# SRH_V2_0.net
KiCad netlist of a schematic drawn in EasyEDA Pro
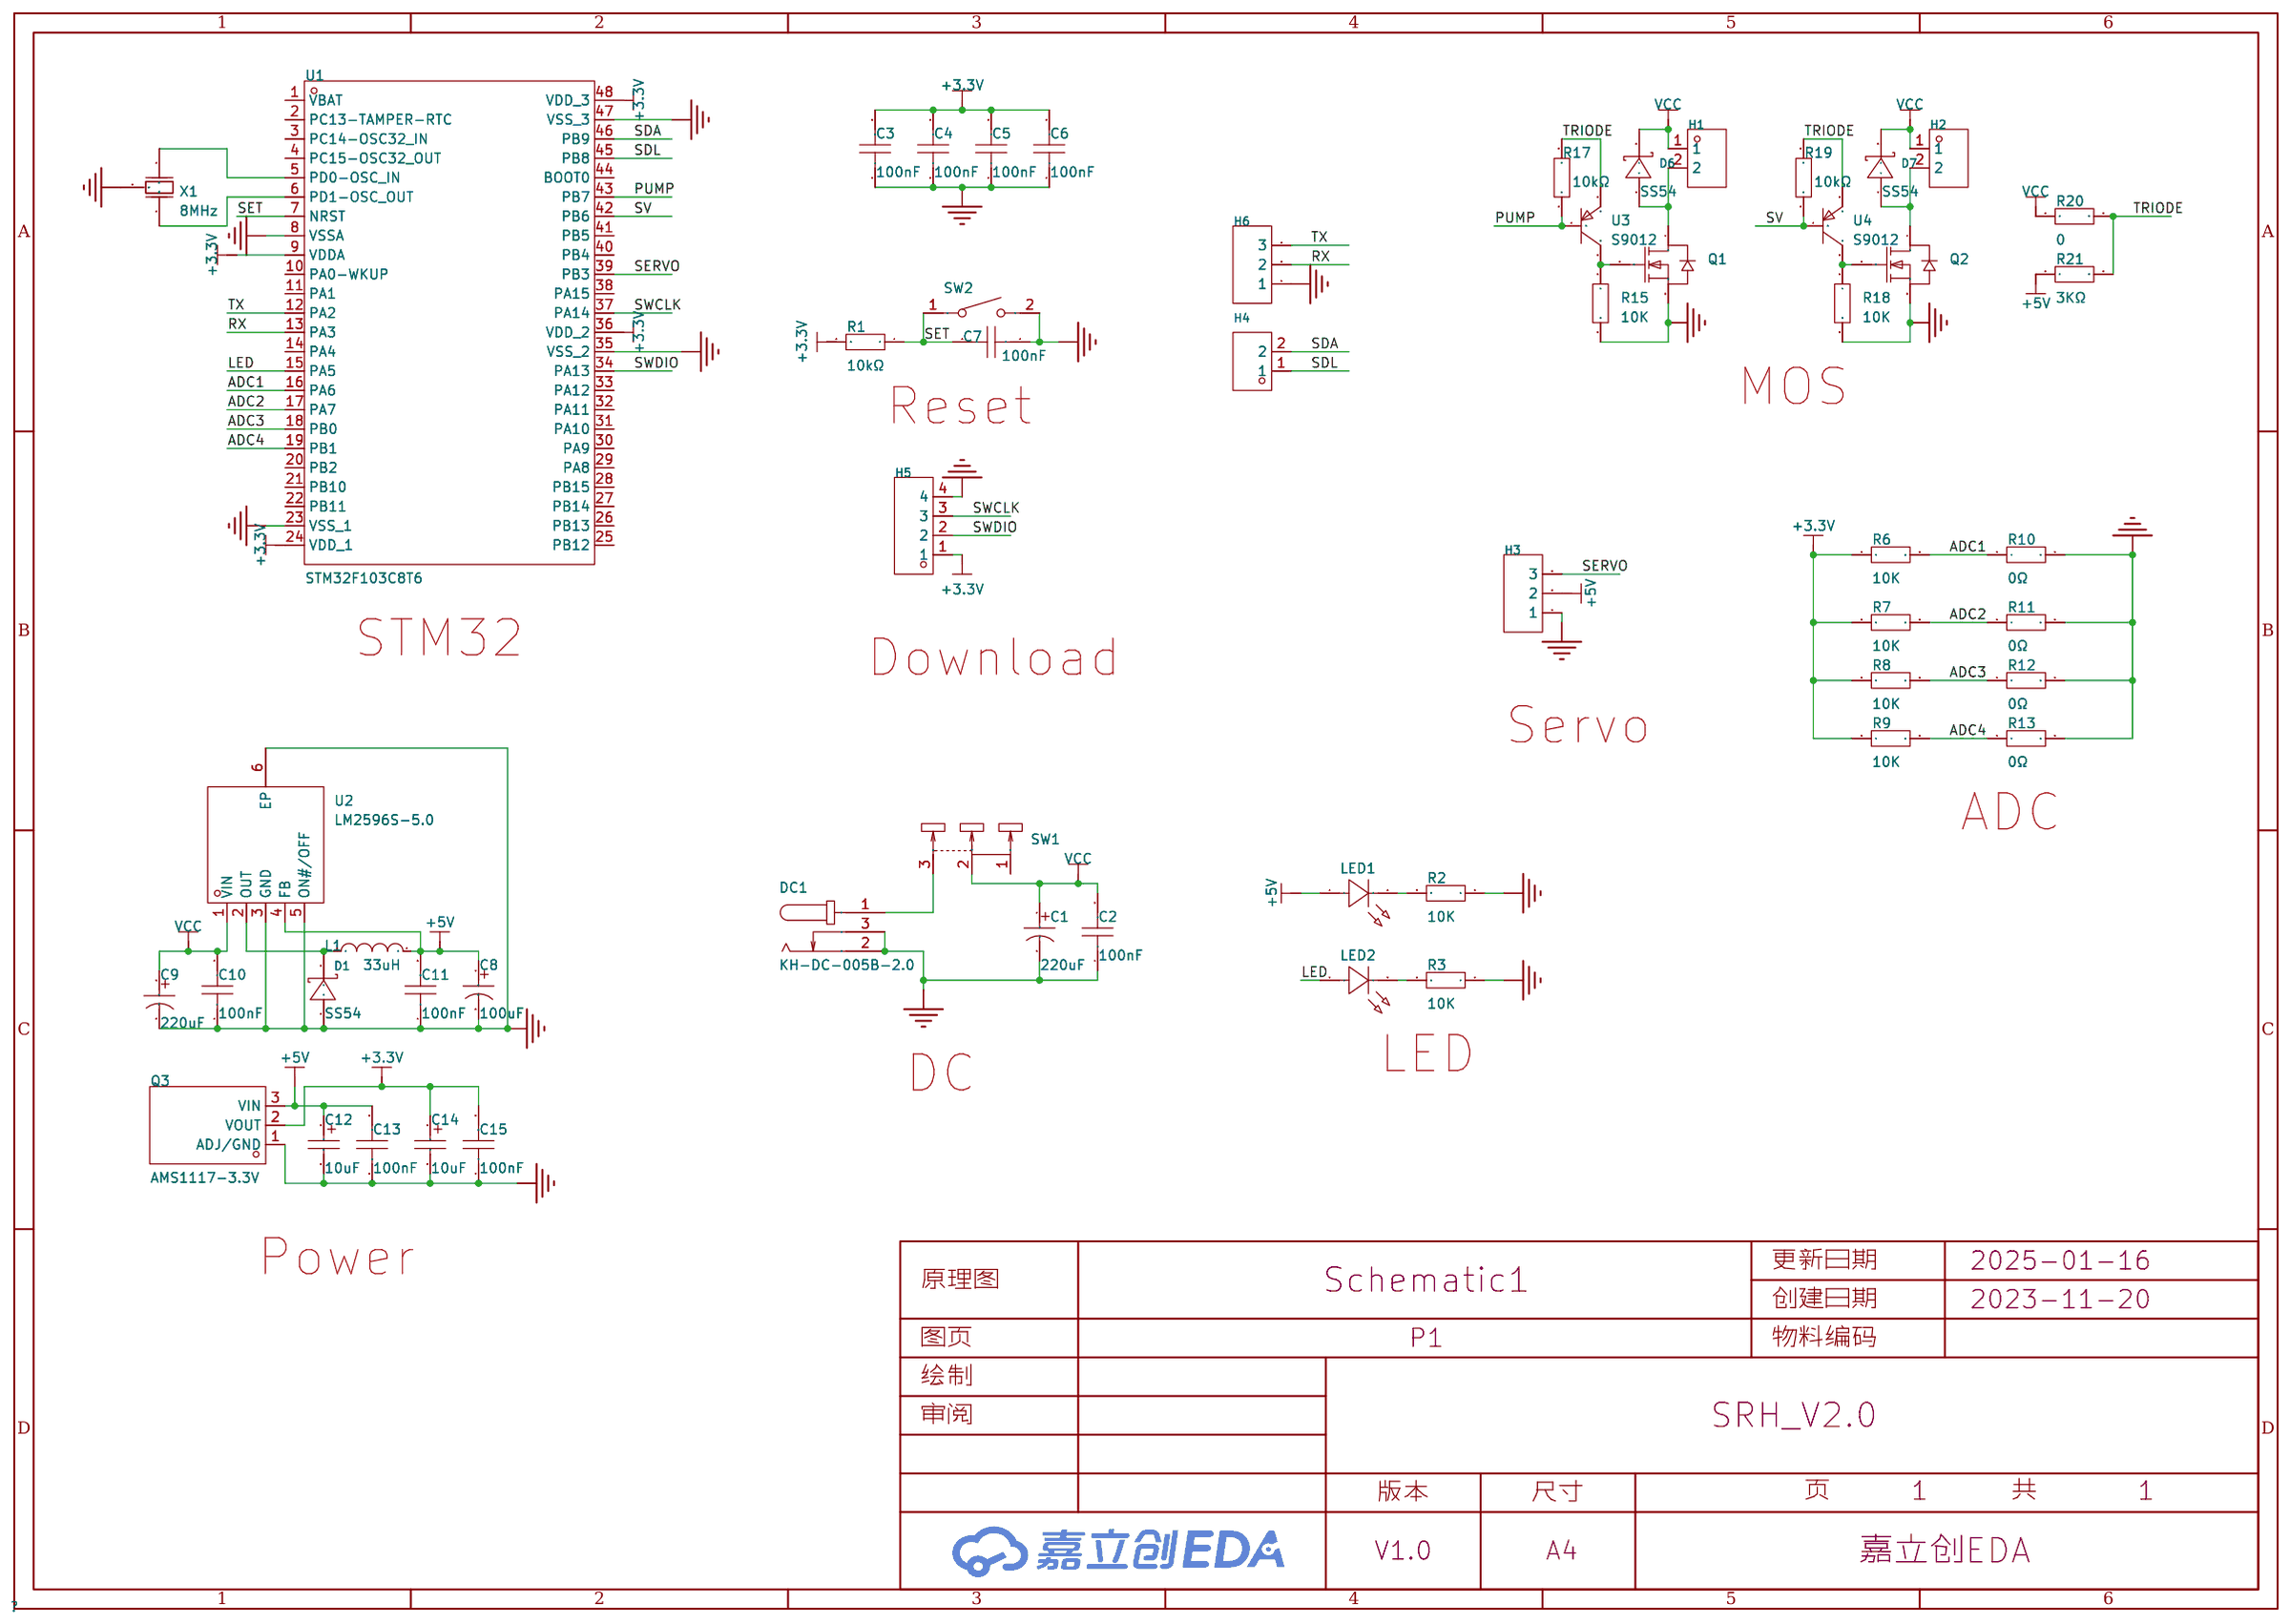
[diagram p0: schematic sheet]

(export (version "E")
  (design (tool "Eeschema 10.0.6"))
  (components
    (comp (ref "C1")
      (value "220uF")
      (footprint "easyedapro:CAP-TH_BD6.3-P2.50-D1.0-FD")
      (description "容值:220uF;精度:±20%;额定电压:16V;纹波电流:-;等效串联电阻:-;")
      (fields
        (field (name "Manufacturer Part") "KS227M016E07RR0VH2FP0")
        (field (name "Manufacturer") "CX(承兴)")
      )
      (libsource (lib "easyedapro") (part "220uF 16V 6.3*7"))
    )
    (comp (ref "C2")
      (value "100nF")
      (footprint "easyedapro:C0603")
      (libsource (lib "easyedapro") (part "CapAcitance"))
    )
    (comp (ref "C3")
      (value "100nF")
      (footprint "easyedapro:C0603")
      (description "容值:100nF;精度:±10%;额定电压:50V;材质(温度系数):X7R;")
      (fields
        (field (name "Manufacturer Part") "CC0603KRX7R9BB104")
        (field (name "Manufacturer") "YAGEO(国巨)")
      )
      (libsource (lib "easyedapro") (part "CC0603KRX7R9BB104"))
    )
    (comp (ref "C4")
      (value "100nF")
      (footprint "easyedapro:C0603")
      (description "容值:100nF;精度:±10%;额定电压:50V;材质(温度系数):X7R;")
      (fields
        (field (name "Manufacturer Part") "CC0603KRX7R9BB104")
        (field (name "Manufacturer") "YAGEO(国巨)")
      )
      (libsource (lib "easyedapro") (part "CC0603KRX7R9BB104"))
    )
    (comp (ref "C5")
      (value "100nF")
      (footprint "easyedapro:C0603")
      (description "容值:100nF;精度:±10%;额定电压:50V;材质(温度系数):X7R;")
      (fields
        (field (name "Manufacturer Part") "CC0603KRX7R9BB104")
        (field (name "Manufacturer") "YAGEO(国巨)")
      )
      (libsource (lib "easyedapro") (part "CC0603KRX7R9BB104"))
    )
    (comp (ref "C6")
      (value "100nF")
      (footprint "easyedapro:C0603")
      (description "容值:100nF;精度:±10%;额定电压:50V;材质(温度系数):X7R;")
      (fields
        (field (name "Manufacturer Part") "CC0603KRX7R9BB104")
        (field (name "Manufacturer") "YAGEO(国巨)")
      )
      (libsource (lib "easyedapro") (part "CC0603KRX7R9BB104"))
    )
    (comp (ref "C7")
      (value "100nF")
      (footprint "easyedapro:C0603")
      (description "容值:100nF;精度:±10%;额定电压:50V;材质(温度系数):X7R;")
      (fields
        (field (name "Manufacturer Part") "CC0603KRX7R9BB104")
        (field (name "Manufacturer") "YAGEO(国巨)")
      )
      (libsource (lib "easyedapro") (part "CC0603KRX7R9BB104"))
    )
    (comp (ref "C8")
      (value "100uF")
      (footprint "easyedapro:CAP-TH_BD5.0-P2.00-D0.8-FD")
      (description "容值:100uF;精度:±20%;额定电压:10V;纹波电流:50mA@120Hz;等效串联电阻:-;")
      (fields
        (field (name "Manufacturer Part") "KS107M010D07RR0VH2FP0")
        (field (name "Manufacturer") "CX(承兴)")
      )
      (libsource (lib "easyedapro") (part "100uF 10V 5*7"))
    )
    (comp (ref "C9")
      (value "220uF")
      (footprint "easyedapro:CAP-TH_BD6.3-P2.50-D1.0-FD")
      (description "容值:220uF;精度:±20%;额定电压:16V;纹波电流:-;等效串联电阻:-;")
      (fields
        (field (name "Manufacturer Part") "KS227M016E07RR0VH2FP0")
        (field (name "Manufacturer") "CX(承兴)")
      )
      (libsource (lib "easyedapro") (part "220uF 16V 6.3*7"))
    )
    (comp (ref "C10")
      (value "100nF")
      (footprint "easyedapro:C0603")
      (description "容值:100nF;精度:±10%;额定电压:50V;材质(温度系数):X7R;")
      (fields
        (field (name "Manufacturer Part") "CC0603KRX7R9BB104")
        (field (name "Manufacturer") "YAGEO(国巨)")
      )
      (libsource (lib "easyedapro") (part "CC0603KRX7R9BB104"))
    )
    (comp (ref "C11")
      (value "100nF")
      (footprint "easyedapro:C0603")
      (description "容值:100nF;精度:±10%;额定电压:50V;材质(温度系数):X7R;")
      (fields
        (field (name "Manufacturer Part") "CC0603KRX7R9BB104")
        (field (name "Manufacturer") "YAGEO(国巨)")
      )
      (libsource (lib "easyedapro") (part "CC0603KRX7R9BB104"))
    )
    (comp (ref "C12")
      (value "10uF")
      (footprint "easyedapro:CASE-A_3216")
      (description "容值:10uF;精度:±10%;额定电压:16V;等效串联电阻:7Ω@100kHz;")
      (fields
        (field (name "Manufacturer Part") "CA45A-A-16V-10uF-K")
        (field (name "Manufacturer") "CEC(振华新云)")
      )
      (libsource (lib "easyedapro") (part "CA45A-A-16V-10UF-K"))
    )
    (comp (ref "C13")
      (value "100nF")
      (footprint "easyedapro:C0603")
      (libsource (lib "easyedapro") (part "CapAcitance"))
    )
    (comp (ref "C14")
      (value "10uF")
      (footprint "easyedapro:CASE-A_3216")
      (description "容值:10uF;精度:±10%;额定电压:16V;等效串联电阻:7Ω@100kHz;")
      (fields
        (field (name "Manufacturer Part") "CA45A-A-16V-10uF-K")
        (field (name "Manufacturer") "CEC(振华新云)")
      )
      (libsource (lib "easyedapro") (part "CA45A-A-16V-10UF-K"))
    )
    (comp (ref "C15")
      (value "100nF")
      (footprint "easyedapro:C0603")
      (libsource (lib "easyedapro") (part "CapAcitance"))
    )
    (comp (ref "D1")
      (value "SS54")
      (footprint "easyedapro:SMA_L4.4-W2.8-LS5.4-R-RD")
      (description "直流反向耐压（Vr）:40V;平均整流电流（Io）:5A;正向压降（Vf）:550mV @ 5A;")
      (fields (field (name "Manufacturer") "MDD"))
      (libsource (lib "easyedapro") (part "SS54_C22452"))
    )
    (comp (ref "D6")
      (value "SS54")
      (footprint "easyedapro:SMA_L4.4-W2.8-LS5.4-R-RD")
      (description "直流反向耐压（Vr）:40V;平均整流电流（Io）:5A;正向压降（Vf）:550mV @ 5A;")
      (fields (field (name "Manufacturer") "MDD"))
      (libsource (lib "easyedapro") (part "SS54_C22452"))
    )
    (comp (ref "D7")
      (value "SS54")
      (footprint "easyedapro:SMA_L4.4-W2.8-LS5.4-R-RD")
      (description "直流反向耐压（Vr）:40V;平均整流电流（Io）:5A;正向压降（Vf）:550mV @ 5A;")
      (fields (field (name "Manufacturer") "MDD"))
      (libsource (lib "easyedapro") (part "SS54_C22452"))
    )
    (comp (ref "DC1")
      (value "KH-DC-005B-2.0")
      (footprint "easyedapro:DC-IN-TH_KH-DC-005B-2.0")
      (description "连接器类型:DC电源插座;安装方式:弯插;触点内径:2mm;触点外径:6.3mm;额定电流:500mA;额定电压:30V;工作温度范围:-30°C~+70°C;")
      (fields (field (name "Manufacturer") "kinghelm(金航标)"))
      (libsource (lib "easyedapro") (part "KH-DC-005B-2.0"))
    )
    (comp (ref "H1")
      (value "PZ254V-11-02P")
      (footprint "easyedapro:HDR-TH_2P-P2.54-V-M")
      (fields (field (name "Manufacturer") "XFCN(兴飞)"))
      (libsource (lib "easyedapro") (part "PZ254V-11-02P"))
    )
    (comp (ref "H2")
      (value "PZ254V-11-02P")
      (footprint "easyedapro:HDR-TH_2P-P2.54-V-M")
      (fields (field (name "Manufacturer") "XFCN(兴飞)"))
      (libsource (lib "easyedapro") (part "PZ254V-11-02P"))
    )
    (comp (ref "H3")
      (value "2.54-1*3P针")
      (footprint "easyedapro:HDR-TH_3P-P2.54-V-M-1")
      (fields (field (name "Manufacturer") "BOOMELE(博穆精密)"))
      (libsource (lib "easyedapro") (part "Header-Male-2.54_1x3"))
    )
    (comp (ref "H4")
      (value "PZ254V-11-02P")
      (footprint "easyedapro:HDR-TH_2P-P2.54-V-M")
      (fields (field (name "Manufacturer") "XFCN(兴飞)"))
      (libsource (lib "easyedapro") (part "PZ254V-11-02P"))
    )
    (comp (ref "H5")
      (value "PZ254V-11-04P")
      (footprint "easyedapro:HDR-TH_4P-P2.54-V-M")
      (fields (field (name "Manufacturer") "XFCN(兴飞)"))
      (libsource (lib "easyedapro") (part "PZ254V-11-04P_C2691448"))
    )
    (comp (ref "H6")
      (value "2.54-1*3P针")
      (footprint "easyedapro:HDR-TH_3P-P2.54-V-M-1")
      (fields (field (name "Manufacturer") "BOOMELE(博穆精密)"))
      (libsource (lib "easyedapro") (part "Header-Male-2.54_1x3"))
    )
    (comp (ref "L1")
      (value "33uH")
      (footprint "easyedapro:IND-SMD_L7.5-W7.5_CYH74")
      (description "类型:-;电感值:33uH;精度:±20%;额定电流:-;饱和电流(Isat):-;")
      (fields (field (name "Manufacturer Part") "CYH74-33UH") (field (name "Manufacturer") "SHOU HAN(首韩)"))
      (libsource (lib "easyedapro") (part "CYH74-33UH"))
    )
    (comp (ref "LED1")
      (value "19-213/GHC-ZN2Q1B8X/3T")
      (footprint "easyedapro:LED-SMD_L1.6-W0.8-RD-2")
      (fields (field (name "Manufacturer") "EVERLIGHT(亿光)"))
      (libsource (lib "easyedapro") (part "19-213/GHC-ZN2Q1B8X/3T"))
    )
    (comp (ref "LED2")
      (value "19-213/GHC-ZN2Q1B8X/3T")
      (footprint "easyedapro:LED-SMD_L1.6-W0.8-RD-2")
      (fields (field (name "Manufacturer") "EVERLIGHT(亿光)"))
      (libsource (lib "easyedapro") (part "19-213/GHC-ZN2Q1B8X/3T"))
    )
    (comp (ref "Q1")
      (value "IRLR7843TRPBF")
      (footprint "easyedapro:TO-252-2_L6.5-W6.1-P4.58-LS10.0-TR")
      (fields (field (name "Manufacturer") "Infineon(英飞凌)"))
      (libsource (lib "easyedapro") (part "IRLR7843TRPBF"))
    )
    (comp (ref "Q2")
      (value "IRLR7843TRPBF")
      (footprint "easyedapro:TO-252-2_L6.5-W6.1-P4.58-LS10.0-TR")
      (fields (field (name "Manufacturer") "Infineon(英飞凌)"))
      (libsource (lib "easyedapro") (part "IRLR7843TRPBF"))
    )
    (comp (ref "Q3")
      (value "AMS1117-3.3V")
      (footprint "easyedapro:SOT-89-3_L4.5-W2.5-P1.50-LS4.2-BR")
      (description "输出类型:固定;输出极性:正;最大输入电压:18V;输出电压:3.3V;输出电流:1A;")
      (fields (field (name "Manufacturer") "MSKSEMI(美森科)"))
      (libsource (lib "easyedapro") (part "AMS1117-3.3V_C5120796"))
    )
    (comp (ref "R1")
      (value "10kΩ")
      (footprint "easyedapro:R0603")
      (description "电阻类型:厚膜电阻;阻值:10kΩ;精度:±1%;功率:100mW;")
      (fields
        (field (name "Manufacturer Part") "0603WAF1002T5E")
        (field (name "Manufacturer") "UNI-ROYAL(厚声)")
      )
      (libsource (lib "easyedapro") (part "0603WAF1002T5E"))
    )
    (comp (ref "R2") (value "10K") (footprint "easyedapro:R0603") (libsource (lib "easyedapro") (part "电阻")))
    (comp (ref "R3") (value "10K") (footprint "easyedapro:R0603") (libsource (lib "easyedapro") (part "电阻")))
    (comp (ref "R6") (value "10K") (footprint "easyedapro:R0603") (libsource (lib "easyedapro") (part "电阻")))
    (comp (ref "R7") (value "10K") (footprint "easyedapro:R0603") (libsource (lib "easyedapro") (part "电阻")))
    (comp (ref "R8") (value "10K") (footprint "easyedapro:R0603") (libsource (lib "easyedapro") (part "电阻")))
    (comp (ref "R9") (value "10K") (footprint "easyedapro:R0603") (libsource (lib "easyedapro") (part "电阻")))
    (comp (ref "R10")
      (value "0Ω")
      (footprint "easyedapro:R1206")
      (description "电阻类型:厚膜电阻;阻值:0Ω;精度:±1%;功率:250mW;温度系数:±800ppm/°C;最大工作电压:200V;工作温度范围:-55°C~+155°C;")
      (fields
        (field (name "Manufacturer Part") "1206W4F0000T5E")
        (field (name "Manufacturer") "UNI-ROYAL(厚声)")
      )
      (libsource (lib "easyedapro") (part "1206W4F0000T5E"))
    )
    (comp (ref "R11")
      (value "0Ω")
      (footprint "easyedapro:R1206")
      (description "电阻类型:厚膜电阻;阻值:0Ω;精度:±1%;功率:250mW;温度系数:±800ppm/°C;最大工作电压:200V;工作温度范围:-55°C~+155°C;")
      (fields
        (field (name "Manufacturer Part") "1206W4F0000T5E")
        (field (name "Manufacturer") "UNI-ROYAL(厚声)")
      )
      (libsource (lib "easyedapro") (part "1206W4F0000T5E"))
    )
    (comp (ref "R12")
      (value "0Ω")
      (footprint "easyedapro:R1206")
      (description "电阻类型:厚膜电阻;阻值:0Ω;精度:±1%;功率:250mW;温度系数:±800ppm/°C;最大工作电压:200V;工作温度范围:-55°C~+155°C;")
      (fields
        (field (name "Manufacturer Part") "1206W4F0000T5E")
        (field (name "Manufacturer") "UNI-ROYAL(厚声)")
      )
      (libsource (lib "easyedapro") (part "1206W4F0000T5E"))
    )
    (comp (ref "R13")
      (value "0Ω")
      (footprint "easyedapro:R1206")
      (description "电阻类型:厚膜电阻;阻值:0Ω;精度:±1%;功率:250mW;温度系数:±800ppm/°C;最大工作电压:200V;工作温度范围:-55°C~+155°C;")
      (fields
        (field (name "Manufacturer Part") "1206W4F0000T5E")
        (field (name "Manufacturer") "UNI-ROYAL(厚声)")
      )
      (libsource (lib "easyedapro") (part "1206W4F0000T5E"))
    )
    (comp (ref "R15") (value "10K") (footprint "easyedapro:R0603") (libsource (lib "easyedapro") (part "电阻")))
    (comp (ref "R17")
      (value "10kΩ")
      (footprint "easyedapro:R0603")
      (description "电阻类型:厚膜电阻;阻值:10kΩ;精度:±1%;功率:100mW;")
      (fields
        (field (name "Manufacturer Part") "0603WAF1002T5E")
        (field (name "Manufacturer") "UNI-ROYAL(厚声)")
      )
      (libsource (lib "easyedapro") (part "0603WAF1002T5E"))
    )
    (comp (ref "R18") (value "10K") (footprint "easyedapro:R0603") (libsource (lib "easyedapro") (part "电阻")))
    (comp (ref "R19")
      (value "10kΩ")
      (footprint "easyedapro:R0603")
      (description "电阻类型:厚膜电阻;阻值:10kΩ;精度:±1%;功率:100mW;")
      (fields
        (field (name "Manufacturer Part") "0603WAF1002T5E")
        (field (name "Manufacturer") "UNI-ROYAL(厚声)")
      )
      (libsource (lib "easyedapro") (part "0603WAF1002T5E"))
    )
    (comp (ref "R20") (value "0") (footprint "easyedapro:R0603") (libsource (lib "easyedapro") (part "电阻")))
    (comp (ref "R21") (value "3KΩ") (footprint "easyedapro:R0603") (libsource (lib "easyedapro") (part "电阻")))
    (comp (ref "SW1")
      (value "SS-12D10L3")
      (footprint "easyedapro:SW-TH_SS-12D10L3")
      (description "额定电流(DC):3A;额定电压(DC):125V;额定电流(AC):3A;额定电压(AC):125V;电路结构:单刀双掷;安装方式:直插;机械寿命:1万次;开关颜色:黑色;")
      (fields (field (name "Manufacturer") "XKB Connectivity(中国星坤)"))
      (libsource (lib "easyedapro") (part "SS-12D10L3"))
    )
    (comp (ref "SW2")
      (value "TS-1185EC-C-D-B")
      (footprint "easyedapro:SW-SMD_4P-L3.7-W3.0-P1.50-LS4.7")
      (description "触点电流:50mA;额定电压(DC):12V;绝缘电阻:-;电路结构:单刀单掷;安装方式:立贴;带灯:无;作用力:260gf;机械寿命:10万次;带支架:否;")
      (fields (field (name "Manufacturer") "XKB Connectivity(中国星坤)"))
      (libsource (lib "easyedapro") (part "TS-1185EC-C-D-B"))
    )
    (comp (ref "U1")
      (value "STM32F103C8T6")
      (footprint "easyedapro:LQFP-48_L7.0-W7.0-P0.50-LS9.0-BL")
      (fields (field (name "Manufacturer") "ST(意法半导体)"))
      (libsource (lib "easyedapro") (part "STM32F103C8T6"))
    )
    (comp (ref "U2")
      (value "LM2596S-5.0")
      (footprint "easyedapro:TO-263-5_L10.2-W8.9-P1.70-BR")
      (description "功能类型:降压型;输出类型:固定;输入电压:40V;输出电压:5V;输出电流(最大值):3A;")
      (fields (field (name "Manufacturer") "UMW(广东友台半导体)"))
      (libsource (lib "easyedapro") (part "LM2596S-5.0"))
    )
    (comp (ref "U3")
      (value "S9012")
      (footprint "easyedapro:SOT-23-3_L2.9-W1.4-P1.90-LS2.6-BR")
      (description "晶体管类型：PNP 集射极击穿电压(Vceo)：25V 集电极电流(Ic)：500mA 功率(Pd)：300mW")
      (fields (field (name "Manufacturer") "TWGMC(台湾迪嘉)"))
      (libsource (lib "easyedapro") (part "S9012_C5204710"))
    )
    (comp (ref "U4")
      (value "S9012")
      (footprint "easyedapro:SOT-23-3_L2.9-W1.4-P1.90-LS2.6-BR")
      (description "晶体管类型：PNP 集射极击穿电压(Vceo)：25V 集电极电流(Ic)：500mA 功率(Pd)：300mW")
      (fields (field (name "Manufacturer") "TWGMC(台湾迪嘉)"))
      (libsource (lib "easyedapro") (part "S9012_C5204710"))
    )
    (comp (ref "X1")
      (value "8MHz")
      (footprint "easyedapro:OSC-SMD_3P-L3.2-W1.3-P1.2-L")
      (description "频率:8MHz;频率容差:±0.5%;内置负载电容:33pF;谐振阻抗:40Ω;")
      (fields
        (field (name "Manufacturer Part") "CSTNE8M00G55A000R0")
        (field (name "Manufacturer") "muRata(村田)")
      )
      (libsource (lib "easyedapro") (part "CSTNE8M00G55A000R0"))
    )
  )
  (nets
    (net (code "1") (name "+3.3V") (class "Default")
      (node (ref "C14") (pin "1") (pinfunction "1_1") (pintype "input"))
      (node (ref "C15") (pin "2") (pinfunction "2_2") (pintype "input"))
      (node (ref "C3") (pin "2") (pinfunction "2_2") (pintype "input"))
      (node (ref "C4") (pin "2") (pinfunction "2_2") (pintype "input"))
      (node (ref "C5") (pin "2") (pinfunction "2_2") (pintype "input"))
      (node (ref "C6") (pin "2") (pinfunction "2_2") (pintype "input"))
      (node (ref "H5") (pin "1") (pinfunction "1_1") (pintype "input"))
      (node (ref "Q3") (pin "2") (pinfunction "VOUT_2") (pintype "unspecified"))
      (node (ref "R1") (pin "2") (pinfunction "2_2") (pintype "input"))
      (node (ref "R6") (pin "1") (pinfunction "1_1") (pintype "input"))
      (node (ref "R7") (pin "1") (pinfunction "1_1") (pintype "input"))
      (node (ref "R8") (pin "1") (pinfunction "1_1") (pintype "input"))
      (node (ref "R9") (pin "1") (pinfunction "1_1") (pintype "input"))
      (node (ref "U1") (pin "24") (pinfunction "VDD_1_24") (pintype "unspecified"))
      (node (ref "U1") (pin "36") (pinfunction "VDD_2_36") (pintype "unspecified"))
      (node (ref "U1") (pin "48") (pinfunction "VDD_3_48") (pintype "unspecified"))
      (node (ref "U1") (pin "9") (pinfunction "VDDA_9") (pintype "unspecified"))
    )
    (net (code "2") (name "+5V") (class "Default")
      (node (ref "C11") (pin "2") (pinfunction "2_2") (pintype "input"))
      (node (ref "C12") (pin "1") (pinfunction "1_1") (pintype "input"))
      (node (ref "C13") (pin "2") (pinfunction "2_2") (pintype "input"))
      (node (ref "C8") (pin "1") (pinfunction "1_1") (pintype "input"))
      (node (ref "H3") (pin "2") (pinfunction "2_2") (pintype "input"))
      (node (ref "L1") (pin "2") (pinfunction "2_2") (pintype "input"))
      (node (ref "LED1") (pin "1") (pinfunction "A_1") (pintype "input"))
      (node (ref "Q3") (pin "3") (pinfunction "VIN_3") (pintype "unspecified"))
      (node (ref "R21") (pin "1") (pinfunction "1_1") (pintype "input"))
      (node (ref "U2") (pin "4") (pinfunction "FB_4") (pintype "input"))
    )
    (net (code "3") (name "/ADC1") (class "Default")
      (node (ref "R10") (pin "1") (pinfunction "1_1") (pintype "input"))
      (node (ref "R6") (pin "2") (pinfunction "2_2") (pintype "input"))
      (node (ref "U1") (pin "16") (pinfunction "PA6_16") (pintype "unspecified"))
    )
    (net (code "4") (name "/ADC2") (class "Default")
      (node (ref "R11") (pin "1") (pinfunction "1_1") (pintype "input"))
      (node (ref "R7") (pin "2") (pinfunction "2_2") (pintype "input"))
      (node (ref "U1") (pin "17") (pinfunction "PA7_17") (pintype "unspecified"))
    )
    (net (code "5") (name "/ADC3") (class "Default")
      (node (ref "R12") (pin "1") (pinfunction "1_1") (pintype "input"))
      (node (ref "R8") (pin "2") (pinfunction "2_2") (pintype "input"))
      (node (ref "U1") (pin "18") (pinfunction "PB0_18") (pintype "unspecified"))
    )
    (net (code "6") (name "/ADC4") (class "Default")
      (node (ref "R13") (pin "1") (pinfunction "1_1") (pintype "input"))
      (node (ref "R9") (pin "2") (pinfunction "2_2") (pintype "input"))
      (node (ref "U1") (pin "19") (pinfunction "PB1_19") (pintype "unspecified"))
    )
    (net (code "7") (name "/LED") (class "Default")
      (node (ref "LED2") (pin "1") (pinfunction "A_1") (pintype "input"))
      (node (ref "U1") (pin "15") (pinfunction "PA5_15") (pintype "unspecified"))
    )
    (net (code "8") (name "/PUMP") (class "Default")
      (node (ref "R17") (pin "1") (pinfunction "1_1") (pintype "input"))
      (node (ref "U1") (pin "43") (pinfunction "PB7_43") (pintype "unspecified"))
      (node (ref "U3") (pin "1") (pinfunction "B_1") (pintype "input"))
    )
    (net (code "9") (name "/RX") (class "Default")
      (node (ref "H6") (pin "2") (pinfunction "2_2") (pintype "input"))
      (node (ref "U1") (pin "13") (pinfunction "PA3_13") (pintype "unspecified"))
    )
    (net (code "10") (name "/SDA") (class "Default")
      (node (ref "H4") (pin "2") (pinfunction "2_2") (pintype "input"))
      (node (ref "U1") (pin "46") (pinfunction "PB9_46") (pintype "unspecified"))
    )
    (net (code "11") (name "/SDL") (class "Default")
      (node (ref "H4") (pin "1") (pinfunction "1_1") (pintype "input"))
      (node (ref "U1") (pin "45") (pinfunction "PB8_45") (pintype "unspecified"))
    )
    (net (code "12") (name "/SERVO") (class "Default")
      (node (ref "H3") (pin "3") (pinfunction "3_3") (pintype "input"))
      (node (ref "U1") (pin "39") (pinfunction "PB3_39") (pintype "unspecified"))
    )
    (net (code "13") (name "/SET") (class "Default")
      (node (ref "C7") (pin "2") (pinfunction "2_2") (pintype "input"))
      (node (ref "R1") (pin "1") (pinfunction "1_1") (pintype "input"))
      (node (ref "SW2") (pin "1") (pinfunction "1_1") (pintype "input"))
      (node (ref "U1") (pin "7") (pinfunction "NRST_7") (pintype "unspecified"))
    )
    (net (code "14") (name "/SV") (class "Default")
      (node (ref "R19") (pin "1") (pinfunction "1_1") (pintype "input"))
      (node (ref "U1") (pin "42") (pinfunction "PB6_42") (pintype "unspecified"))
      (node (ref "U4") (pin "1") (pinfunction "B_1") (pintype "input"))
    )
    (net (code "15") (name "/SWCLK") (class "Default")
      (node (ref "H5") (pin "3") (pinfunction "3_3") (pintype "input"))
      (node (ref "U1") (pin "37") (pinfunction "PA14_37") (pintype "unspecified"))
    )
    (net (code "16") (name "/SWDIO") (class "Default")
      (node (ref "H5") (pin "2") (pinfunction "2_2") (pintype "input"))
      (node (ref "U1") (pin "34") (pinfunction "PA13_34") (pintype "unspecified"))
    )
    (net (code "17") (name "/TRIODE") (class "Default")
      (node (ref "R17") (pin "2") (pinfunction "2_2") (pintype "input"))
      (node (ref "R19") (pin "2") (pinfunction "2_2") (pintype "input"))
      (node (ref "R20") (pin "2") (pinfunction "2_2") (pintype "input"))
      (node (ref "R21") (pin "2") (pinfunction "2_2") (pintype "input"))
      (node (ref "U3") (pin "2") (pinfunction "E_2") (pintype "input"))
      (node (ref "U4") (pin "2") (pinfunction "E_2") (pintype "input"))
    )
    (net (code "18") (name "/TX") (class "Default")
      (node (ref "H6") (pin "3") (pinfunction "3_3") (pintype "input"))
      (node (ref "U1") (pin "12") (pinfunction "PA2_12") (pintype "unspecified"))
    )
    (net (code "19") (name "GND") (class "Default")
      (node (ref "C1") (pin "2") (pinfunction "2_2") (pintype "input"))
      (node (ref "C10") (pin "1") (pinfunction "1_1") (pintype "input"))
      (node (ref "C11") (pin "1") (pinfunction "1_1") (pintype "input"))
      (node (ref "C12") (pin "2") (pinfunction "2_2") (pintype "input"))
      (node (ref "C13") (pin "1") (pinfunction "1_1") (pintype "input"))
      (node (ref "C14") (pin "2") (pinfunction "2_2") (pintype "input"))
      (node (ref "C15") (pin "1") (pinfunction "1_1") (pintype "input"))
      (node (ref "C2") (pin "1") (pinfunction "1_1") (pintype "input"))
      (node (ref "C3") (pin "1") (pinfunction "1_1") (pintype "input"))
      (node (ref "C4") (pin "1") (pinfunction "1_1") (pintype "input"))
      (node (ref "C5") (pin "1") (pinfunction "1_1") (pintype "input"))
      (node (ref "C6") (pin "1") (pinfunction "1_1") (pintype "input"))
      (node (ref "C7") (pin "1") (pinfunction "1_1") (pintype "input"))
      (node (ref "C8") (pin "2") (pinfunction "2_2") (pintype "input"))
      (node (ref "C9") (pin "2") (pinfunction "2_2") (pintype "input"))
      (node (ref "D1") (pin "1") (pinfunction "A_1") (pintype "input"))
      (node (ref "DC1") (pin "2") (pinfunction "2_2") (pintype "input"))
      (node (ref "DC1") (pin "3") (pinfunction "3_3") (pintype "input"))
      (node (ref "H3") (pin "1") (pinfunction "1_1") (pintype "input"))
      (node (ref "H5") (pin "4") (pinfunction "4_4") (pintype "input"))
      (node (ref "H6") (pin "1") (pinfunction "1_1") (pintype "input"))
      (node (ref "Q1") (pin "3") (pinfunction "S_3") (pintype "input"))
      (node (ref "Q2") (pin "3") (pinfunction "S_3") (pintype "input"))
      (node (ref "Q3") (pin "1") (pinfunction "ADJ/GND_1") (pintype "unspecified"))
      (node (ref "R10") (pin "2") (pinfunction "2_2") (pintype "input"))
      (node (ref "R11") (pin "2") (pinfunction "2_2") (pintype "input"))
      (node (ref "R12") (pin "2") (pinfunction "2_2") (pintype "input"))
      (node (ref "R13") (pin "2") (pinfunction "2_2") (pintype "input"))
      (node (ref "R15") (pin "2") (pinfunction "2_2") (pintype "input"))
      (node (ref "R18") (pin "2") (pinfunction "2_2") (pintype "input"))
      (node (ref "R2") (pin "1") (pinfunction "1_1") (pintype "input"))
      (node (ref "R3") (pin "1") (pinfunction "1_1") (pintype "input"))
      (node (ref "SW2") (pin "2") (pinfunction "2_2") (pintype "input"))
      (node (ref "U1") (pin "23") (pinfunction "VSS_1_23") (pintype "unspecified"))
      (node (ref "U1") (pin "35") (pinfunction "VSS_2_35") (pintype "unspecified"))
      (node (ref "U1") (pin "47") (pinfunction "VSS_3_47") (pintype "unspecified"))
      (node (ref "U1") (pin "8") (pinfunction "VSSA_8") (pintype "unspecified"))
      (node (ref "U2") (pin "3") (pinfunction "GND_3") (pintype "input"))
      (node (ref "U2") (pin "5") (pinfunction "ON#/OFF_5") (pintype "input"))
      (node (ref "U2") (pin "6") (pinfunction "EP_6") (pintype "input"))
      (node (ref "X1") (pin "2") (pinfunction "GND_2") (pintype "input"))
    )
    (net (code "20") (name "Net-(D1-K)") (class "Default")
      (node (ref "D1") (pin "2") (pinfunction "K_2") (pintype "input"))
      (node (ref "L1") (pin "1") (pinfunction "1_1") (pintype "input"))
      (node (ref "U2") (pin "2") (pinfunction "OUT_2") (pintype "input"))
    )
    (net (code "21") (name "Net-(D6-A)") (class "Default")
      (node (ref "D6") (pin "1") (pinfunction "A_1") (pintype "input"))
      (node (ref "H1") (pin "2") (pinfunction "2_2") (pintype "input"))
      (node (ref "Q1") (pin "4") (pinfunction "D_4") (pintype "input"))
    )
    (net (code "22") (name "Net-(D7-A)") (class "Default")
      (node (ref "D7") (pin "1") (pinfunction "A_1") (pintype "input"))
      (node (ref "H2") (pin "2") (pinfunction "2_2") (pintype "input"))
      (node (ref "Q2") (pin "4") (pinfunction "D_4") (pintype "input"))
    )
    (net (code "23") (name "Net-(DC1-Pad1)") (class "Default")
      (node (ref "DC1") (pin "1") (pinfunction "1_1") (pintype "input"))
      (node (ref "SW1") (pin "3") (pinfunction "3_3") (pintype "input"))
    )
    (net (code "24") (name "Net-(LED1-K)") (class "Default")
      (node (ref "LED1") (pin "2") (pinfunction "K_2") (pintype "input"))
      (node (ref "R2") (pin "2") (pinfunction "2_2") (pintype "input"))
    )
    (net (code "25") (name "Net-(LED2-K)") (class "Default")
      (node (ref "LED2") (pin "2") (pinfunction "K_2") (pintype "input"))
      (node (ref "R3") (pin "2") (pinfunction "2_2") (pintype "input"))
    )
    (net (code "26") (name "Net-(Q1-G)") (class "Default")
      (node (ref "Q1") (pin "1") (pinfunction "G_1") (pintype "input"))
      (node (ref "R15") (pin "1") (pinfunction "1_1") (pintype "input"))
      (node (ref "U3") (pin "3") (pinfunction "C_3") (pintype "input"))
    )
    (net (code "27") (name "Net-(Q2-G)") (class "Default")
      (node (ref "Q2") (pin "1") (pinfunction "G_1") (pintype "input"))
      (node (ref "R18") (pin "1") (pinfunction "1_1") (pintype "input"))
      (node (ref "U4") (pin "3") (pinfunction "C_3") (pintype "input"))
    )
    (net (code "28") (name "Net-(U1-PD0-OSC_IN)") (class "Default")
      (node (ref "U1") (pin "5") (pinfunction "PD0-OSC_IN_5") (pintype "unspecified"))
      (node (ref "X1") (pin "3") (pinfunction "OSC2_3") (pintype "input"))
    )
    (net (code "29") (name "Net-(U1-PD1-OSC_OUT)") (class "Default")
      (node (ref "U1") (pin "6") (pinfunction "PD1-OSC_OUT_6") (pintype "unspecified"))
      (node (ref "X1") (pin "1") (pinfunction "OSC1_1") (pintype "input"))
    )
    (net (code "30") (name "VCC") (class "Default")
      (node (ref "C1") (pin "1") (pinfunction "1_1") (pintype "input"))
      (node (ref "C10") (pin "2") (pinfunction "2_2") (pintype "input"))
      (node (ref "C2") (pin "2") (pinfunction "2_2") (pintype "input"))
      (node (ref "C9") (pin "1") (pinfunction "1_1") (pintype "input"))
      (node (ref "D6") (pin "2") (pinfunction "K_2") (pintype "input"))
      (node (ref "D7") (pin "2") (pinfunction "K_2") (pintype "input"))
      (node (ref "H1") (pin "1") (pinfunction "1_1") (pintype "input"))
      (node (ref "H2") (pin "1") (pinfunction "1_1") (pintype "input"))
      (node (ref "R20") (pin "1") (pinfunction "1_1") (pintype "input"))
      (node (ref "SW1") (pin "2") (pinfunction "2_2") (pintype "input"))
      (node (ref "U2") (pin "1") (pinfunction "VIN_1") (pintype "input"))
    )
    (net (code "31") (name "unconnected-(SW1-Pad1)") (class "Default")
      (node (ref "SW1") (pin "1") (pinfunction "1_1") (pintype "input"))
    )
    (net (code "32") (name "unconnected-(U1-BOOT0-Pad44)") (class "Default")
      (node (ref "U1") (pin "44") (pinfunction "BOOT0_44") (pintype "unspecified"))
    )
    (net (code "33") (name "unconnected-(U1-PA0-WKUP-Pad10)") (class "Default")
      (node (ref "U1") (pin "10") (pinfunction "PA0-WKUP_10") (pintype "unspecified"))
    )
    (net (code "34") (name "unconnected-(U1-PA1-Pad11)") (class "Default")
      (node (ref "U1") (pin "11") (pinfunction "PA1_11") (pintype "unspecified"))
    )
    (net (code "35") (name "unconnected-(U1-PA4-Pad14)") (class "Default")
      (node (ref "U1") (pin "14") (pinfunction "PA4_14") (pintype "unspecified"))
    )
    (net (code "36") (name "unconnected-(U1-PA8-Pad29)") (class "Default")
      (node (ref "U1") (pin "29") (pinfunction "PA8_29") (pintype "unspecified"))
    )
    (net (code "37") (name "unconnected-(U1-PA9-Pad30)") (class "Default")
      (node (ref "U1") (pin "30") (pinfunction "PA9_30") (pintype "unspecified"))
    )
    (net (code "38") (name "unconnected-(U1-PA10-Pad31)") (class "Default")
      (node (ref "U1") (pin "31") (pinfunction "PA10_31") (pintype "unspecified"))
    )
    (net (code "39") (name "unconnected-(U1-PA11-Pad32)") (class "Default")
      (node (ref "U1") (pin "32") (pinfunction "PA11_32") (pintype "unspecified"))
    )
    (net (code "40") (name "unconnected-(U1-PA12-Pad33)") (class "Default")
      (node (ref "U1") (pin "33") (pinfunction "PA12_33") (pintype "unspecified"))
    )
    (net (code "41") (name "unconnected-(U1-PA15-Pad38)") (class "Default")
      (node (ref "U1") (pin "38") (pinfunction "PA15_38") (pintype "unspecified"))
    )
    (net (code "42") (name "unconnected-(U1-PB2-Pad20)") (class "Default")
      (node (ref "U1") (pin "20") (pinfunction "PB2_20") (pintype "unspecified"))
    )
    (net (code "43") (name "unconnected-(U1-PB4-Pad40)") (class "Default")
      (node (ref "U1") (pin "40") (pinfunction "PB4_40") (pintype "unspecified"))
    )
    (net (code "44") (name "unconnected-(U1-PB5-Pad41)") (class "Default")
      (node (ref "U1") (pin "41") (pinfunction "PB5_41") (pintype "unspecified"))
    )
    (net (code "45") (name "unconnected-(U1-PB10-Pad21)") (class "Default")
      (node (ref "U1") (pin "21") (pinfunction "PB10_21") (pintype "unspecified"))
    )
    (net (code "46") (name "unconnected-(U1-PB11-Pad22)") (class "Default")
      (node (ref "U1") (pin "22") (pinfunction "PB11_22") (pintype "unspecified"))
    )
    (net (code "47") (name "unconnected-(U1-PB12-Pad25)") (class "Default")
      (node (ref "U1") (pin "25") (pinfunction "PB12_25") (pintype "unspecified"))
    )
    (net (code "48") (name "unconnected-(U1-PB13-Pad26)") (class "Default")
      (node (ref "U1") (pin "26") (pinfunction "PB13_26") (pintype "unspecified"))
    )
    (net (code "49") (name "unconnected-(U1-PB14-Pad27)") (class "Default")
      (node (ref "U1") (pin "27") (pinfunction "PB14_27") (pintype "unspecified"))
    )
    (net (code "50") (name "unconnected-(U1-PB15-Pad28)") (class "Default")
      (node (ref "U1") (pin "28") (pinfunction "PB15_28") (pintype "unspecified"))
    )
    (net (code "51") (name "unconnected-(U1-PC13-TAMPER-RTC-Pad2)") (class "Default")
      (node (ref "U1") (pin "2") (pinfunction "PC13-TAMPER-RTC_2") (pintype "unspecified"))
    )
    (net (code "52") (name "unconnected-(U1-PC14-OSC32_IN-Pad3)") (class "Default")
      (node (ref "U1") (pin "3") (pinfunction "PC14-OSC32_IN_3") (pintype "unspecified"))
    )
    (net (code "53") (name "unconnected-(U1-PC15-OSC32_OUT-Pad4)") (class "Default")
      (node (ref "U1") (pin "4") (pinfunction "PC15-OSC32_OUT_4") (pintype "unspecified"))
    )
    (net (code "54") (name "unconnected-(U1-VBAT-Pad1)") (class "Default")
      (node (ref "U1") (pin "1") (pinfunction "VBAT_1") (pintype "unspecified"))
    )
  )
)
